# parakeet_board.net
KiCad netlist of a schematic drawn in EAGLE
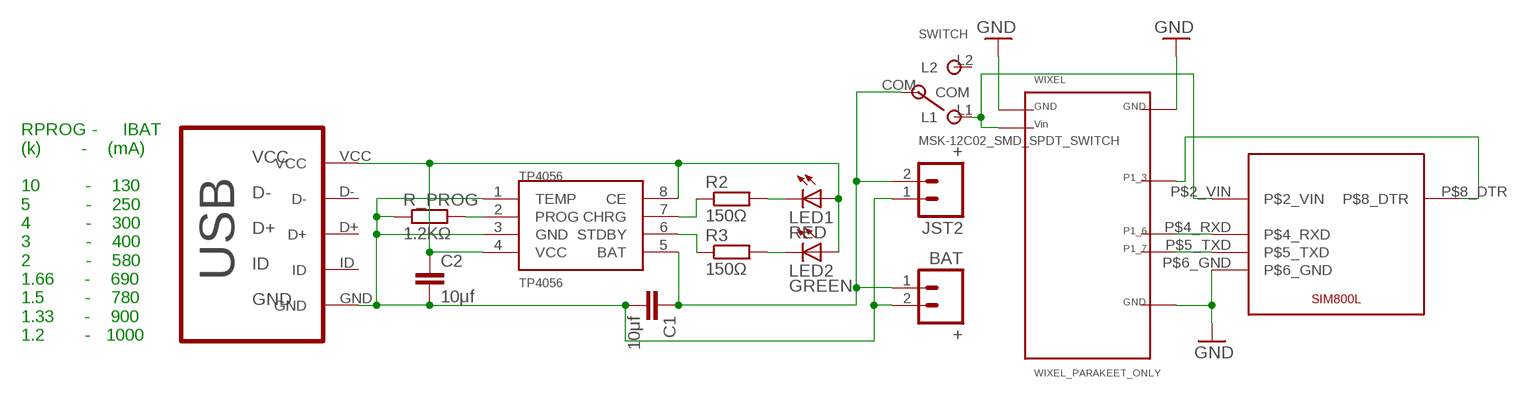
[diagram p0: schematic, sheet 1]

(export (version "E")
  (design (tool "Eeschema 10.0.6"))
  (components
    (comp (ref "+")
      (value "BAT")
      (footprint "eagle-import:1X02")
      (libsource (lib "eagle-import") (part "M02PTH"))
    )
    (comp (ref "C1")
      (value "10μf")
      (footprint "eagle-import:C1206")
      (libsource (lib "eagle-import") (part "C-EUC1206"))
    )
    (comp (ref "C2")
      (value "10μf")
      (footprint "eagle-import:C1206")
      (libsource (lib "eagle-import") (part "C-EUC1206"))
    )
    (comp (ref "JST2")
      (value "+")
      (footprint "eagle-import:JST-2-SMD")
      (libsource (lib "eagle-import") (part "M02-JST-2MM-SMT"))
    )
    (comp (ref "LED1")
      (value "RED")
      (footprint "eagle-import:CHIPLED_1206")
      (libsource (lib "eagle-import") (part "LEDCHIPLED_1206"))
    )
    (comp (ref "LED2")
      (value "GREEN")
      (footprint "eagle-import:CHIPLED_1206")
      (libsource (lib "eagle-import") (part "LEDCHIPLED_1206"))
    )
    (comp (ref "R2")
      (value "150Ω")
      (footprint "eagle-import:R1206")
      (libsource (lib "eagle-import") (part "R-EU_R1206"))
    )
    (comp (ref "R3")
      (value "150Ω")
      (footprint "eagle-import:R1206")
      (libsource (lib "eagle-import") (part "R-EU_R1206"))
    )
    (comp (ref "R_PROG")
      (value "1.2KΩ")
      (footprint "eagle-import:R1206")
      (libsource (lib "eagle-import") (part "R-EU_R1206"))
    )
    (comp (ref "SIM800L")
      (value "SIM800L_PARAKEET_ONLY")
      (footprint "eagle-import:SIM800L_PARAKEET_ONLY")
      (libsource (lib "eagle-import") (part "SIM800L_PARAKEET_ONLY"))
    )
    (comp (ref "SWITCH")
      (value "MSK-12C02_SMD_SPDT_SWITCH")
      (footprint "eagle-import:MSK-12C02")
      (libsource (lib "eagle-import") (part "MSK-12C02_SMD_SPDT_SWITCH"))
    )
    (comp (ref "TP4056")
      (value "TP4056")
      (footprint "eagle-import:SOP-8")
      (libsource (lib "eagle-import") (part "TP4056"))
    )
    (comp (ref "USB")
      (value "MICRO-USB-B")
      (footprint "eagle-import:MICRO_USB_4_LEGS")
      (libsource (lib "eagle-import") (part "MICRO-USB-B"))
    )
    (comp (ref "WIXEL")
      (value "WIXEL_PARAKEET_ONLY")
      (footprint "eagle-import:WIXEL_PARAKEET_ONLY")
      (libsource (lib "eagle-import") (part "WIXEL_PARAKEET_ONLY"))
    )
  )
  (nets
    (net (code "1") (name "GND") (class "Default")
      (node (ref "+") (pin "2") (pinfunction "2_2") (pintype "passive"))
      (node (ref "C1") (pin "2") (pinfunction "2_2") (pintype "passive"))
      (node (ref "C2") (pin "2") (pinfunction "2_2") (pintype "passive"))
      (node (ref "JST2") (pin "1") (pinfunction "2_1") (pintype "passive"))
      (node (ref "R_PROG") (pin "1") (pinfunction "1_1") (pintype "passive"))
      (node (ref "SIM800L") (pin "P$6_GND") (pinfunction "P$6_GND_P$6_GND") (pintype "bidirectional"))
      (node (ref "TP4056") (pin "1") (pinfunction "TEMP_1") (pintype "bidirectional"))
      (node (ref "TP4056") (pin "3") (pinfunction "GND_3") (pintype "bidirectional"))
      (node (ref "USB") (pin "GND") (pinfunction "GND_GND") (pintype "bidirectional"))
      (node (ref "WIXEL") (pin "P$1") (pinfunction "P$1-GND1_P$1") (pintype "bidirectional"))
      (node (ref "WIXEL") (pin "P$12") (pinfunction "P$12-GND2_P$12") (pintype "bidirectional"))
      (node (ref "WIXEL") (pin "P$23") (pinfunction "P$23-GND3_P$23") (pintype "bidirectional"))
    )
    (net (code "2") (name "Net-(JST2-1)") (class "Default")
      (node (ref "+") (pin "1") (pinfunction "1_1") (pintype "passive"))
      (node (ref "C1") (pin "1") (pinfunction "1_1") (pintype "passive"))
      (node (ref "JST2") (pin "2") (pinfunction "1_2") (pintype "passive"))
      (node (ref "SWITCH") (pin "COM") (pinfunction "COM_COM") (pintype "bidirectional"))
      (node (ref "TP4056") (pin "5") (pinfunction "BAT_5") (pintype "bidirectional"))
    )
    (net (code "3") (name "Net-(LED1-PadC)") (class "Default")
      (node (ref "LED1") (pin "C") (pinfunction "C_C") (pintype "passive"))
      (node (ref "R2") (pin "2") (pinfunction "2_2") (pintype "passive"))
    )
    (net (code "4") (name "Net-(LED2-PadC)") (class "Default")
      (node (ref "LED2") (pin "C") (pinfunction "C_C") (pintype "passive"))
      (node (ref "R3") (pin "2") (pinfunction "2_2") (pintype "passive"))
    )
    (net (code "5") (name "Net-(TP4056-CE)") (class "Default")
      (node (ref "C2") (pin "1") (pinfunction "1_1") (pintype "passive"))
      (node (ref "LED1") (pin "A") (pinfunction "A_A") (pintype "passive"))
      (node (ref "LED2") (pin "A") (pinfunction "A_A") (pintype "passive"))
      (node (ref "TP4056") (pin "4") (pinfunction "VCC_4") (pintype "bidirectional"))
      (node (ref "TP4056") (pin "8") (pinfunction "CE_8") (pintype "bidirectional"))
      (node (ref "USB") (pin "VCC") (pinfunction "VCC_VCC") (pintype "bidirectional"))
    )
    (net (code "6") (name "Net-(TP4056-CHRG)") (class "Default")
      (node (ref "R2") (pin "1") (pinfunction "1_1") (pintype "passive"))
      (node (ref "TP4056") (pin "7") (pinfunction "CHRG_7") (pintype "bidirectional"))
    )
    (net (code "7") (name "Net-(TP4056-PROG)") (class "Default")
      (node (ref "R_PROG") (pin "2") (pinfunction "2_2") (pintype "passive"))
      (node (ref "TP4056") (pin "2") (pinfunction "PROG_2") (pintype "bidirectional"))
    )
    (net (code "8") (name "Net-(TP4056-STDBY)") (class "Default")
      (node (ref "R3") (pin "1") (pinfunction "1_1") (pintype "passive"))
      (node (ref "TP4056") (pin "6") (pinfunction "STDBY_6") (pintype "bidirectional"))
    )
    (net (code "9") (name "Net-(WIXEL-P$2-VIN)") (class "Default")
      (node (ref "SIM800L") (pin "P$2_VIN") (pinfunction "P$2_VIN_P$2_VIN") (pintype "bidirectional"))
      (node (ref "SWITCH") (pin "L1") (pinfunction "L1_L1") (pintype "bidirectional"))
      (node (ref "WIXEL") (pin "P$2") (pinfunction "P$2-VIN_P$2") (pintype "bidirectional"))
    )
    (net (code "10") (name "Net-(WIXEL-P$16-P1_3)") (class "Default")
      (node (ref "SIM800L") (pin "P$8_DTR") (pinfunction "P$8_DTR_P$8_DTR") (pintype "bidirectional"))
      (node (ref "WIXEL") (pin "P$16") (pinfunction "P$16-P1_3_P$16") (pintype "bidirectional"))
    )
    (net (code "11") (name "Net-(WIXEL-P$19-P1_6)") (class "Default")
      (node (ref "SIM800L") (pin "P$4_RXD") (pinfunction "P$4_RXD_P$4_RXD") (pintype "bidirectional"))
      (node (ref "WIXEL") (pin "P$19") (pinfunction "P$19-P1_6_P$19") (pintype "bidirectional"))
    )
    (net (code "12") (name "Net-(WIXEL-P$20-P1_7)") (class "Default")
      (node (ref "SIM800L") (pin "P$5_TXD") (pinfunction "P$5_TXD_P$5_TXD") (pintype "bidirectional"))
      (node (ref "WIXEL") (pin "P$20") (pinfunction "P$20-P1_7_P$20") (pintype "bidirectional"))
    )
    (net (code "13") (name "unconnected-(SWITCH-PadL2)") (class "Default")
      (node (ref "SWITCH") (pin "L2") (pinfunction "L2_L2") (pintype "bidirectional"))
    )
    (net (code "14") (name "unconnected-(USB-PadD+)") (class "Default")
      (node (ref "USB") (pin "D+") (pinfunction "D+_D+") (pintype "bidirectional"))
    )
    (net (code "15") (name "unconnected-(USB-PadD-)") (class "Default")
      (node (ref "USB") (pin "D-") (pinfunction "D-_D-") (pintype "bidirectional"))
    )
    (net (code "16") (name "unconnected-(USB-PadID)") (class "Default")
      (node (ref "USB") (pin "ID") (pinfunction "ID_ID") (pintype "bidirectional"))
    )
  )
)
